# Signalwandler.net
KiCad netlist of a schematic drawn in EAGLE
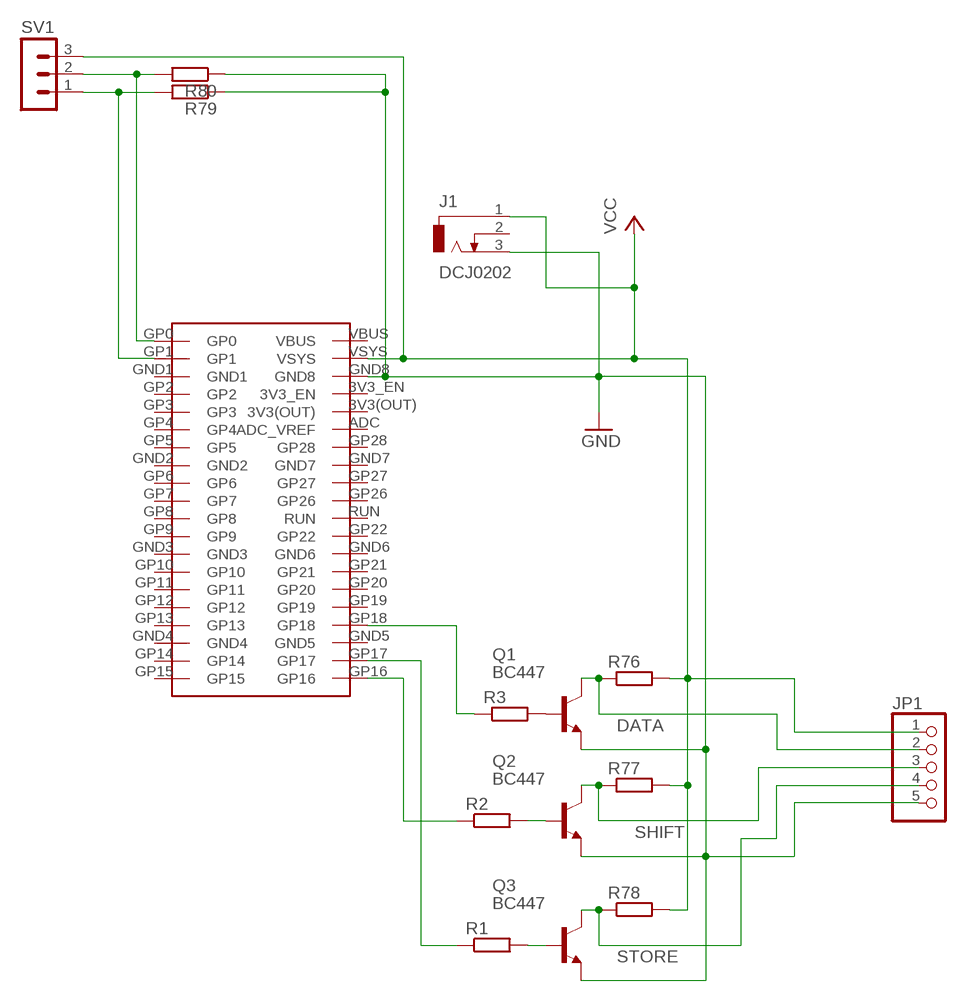
[diagram p0: schematic, sheet 1]

(export (version "E")
  (design (tool "Eeschema 10.0.6"))
  (components
    (comp (ref "J1")
      (value "DCJ0202")
      (footprint "eagle-import:DCJ0202")
      (libsource (lib "eagle-import") (part "DCJ0202"))
    )
    (comp (ref "JP1")
      (value "PINHD-1X5")
      (footprint "eagle-import:1X05")
      (libsource (lib "eagle-import") (part "PINHD-1X5"))
    )
    (comp (ref "Q1")
      (value "BC447")
      (footprint "eagle-import:TO92-EBC")
      (libsource (lib "eagle-import") (part "BC447"))
    )
    (comp (ref "Q2")
      (value "BC447")
      (footprint "eagle-import:TO92-EBC")
      (libsource (lib "eagle-import") (part "BC447"))
    )
    (comp (ref "Q3")
      (value "BC447")
      (footprint "eagle-import:TO92-EBC")
      (libsource (lib "eagle-import") (part "BC447"))
    )
    (comp (ref "R1")
      (value "R-EU_0207/10")
      (footprint "eagle-import:0207_10")
      (libsource (lib "eagle-import") (part "R-EU_0207/10"))
    )
    (comp (ref "R2")
      (value "R-EU_0207/10")
      (footprint "eagle-import:0207_10")
      (libsource (lib "eagle-import") (part "R-EU_0207/10"))
    )
    (comp (ref "R3")
      (value "R-EU_0207/10")
      (footprint "eagle-import:0207_10")
      (libsource (lib "eagle-import") (part "R-EU_0207/10"))
    )
    (comp (ref "R76")
      (value "R-EU_0207/10")
      (footprint "eagle-import:0207_10")
      (libsource (lib "eagle-import") (part "R-EU_0207/10"))
    )
    (comp (ref "R77")
      (value "R-EU_0207/10")
      (footprint "eagle-import:0207_10")
      (libsource (lib "eagle-import") (part "R-EU_0207/10"))
    )
    (comp (ref "R78")
      (value "R-EU_0207/10")
      (footprint "eagle-import:0207_10")
      (libsource (lib "eagle-import") (part "R-EU_0207/10"))
    )
    (comp (ref "R79")
      (value "R-EU_0207/10")
      (footprint "eagle-import:0207_10")
      (libsource (lib "eagle-import") (part "R-EU_0207/10"))
    )
    (comp (ref "R80")
      (value "R-EU_0207/10")
      (footprint "eagle-import:0207_10")
      (libsource (lib "eagle-import") (part "R-EU_0207/10"))
    )
    (comp (ref "SV1")
      (value "MA03-1")
      (footprint "eagle-import:MA03-1")
      (libsource (lib "eagle-import") (part "MA03-1"))
    )
    (comp (ref "U$2")
      (value "PI_PICO")
      (footprint "eagle-import:PI_PICO")
      (libsource (lib "eagle-import") (part "PI_PICO"))
    )
  )
  (nets
    (net (code "1") (name "/DATA") (class "Default")
      (node (ref "JP1") (pin "2") (pinfunction "2_2") (pintype "passive"))
      (node (ref "Q1") (pin "C") (pinfunction "C_C") (pintype "passive"))
      (node (ref "R76") (pin "1") (pinfunction "1_1") (pintype "passive"))
    )
    (net (code "2") (name "/SHIFT") (class "Default")
      (node (ref "JP1") (pin "3") (pinfunction "3_3") (pintype "passive"))
      (node (ref "Q2") (pin "C") (pinfunction "C_C") (pintype "passive"))
      (node (ref "R77") (pin "1") (pinfunction "1_1") (pintype "passive"))
    )
    (net (code "3") (name "/STORE") (class "Default")
      (node (ref "JP1") (pin "4") (pinfunction "4_4") (pintype "passive"))
      (node (ref "Q3") (pin "C") (pinfunction "C_C") (pintype "passive"))
      (node (ref "R78") (pin "1") (pinfunction "1_1") (pintype "passive"))
    )
    (net (code "4") (name "GND") (class "Default")
      (node (ref "J1") (pin "3") (pinfunction "3_3") (pintype "passive"))
      (node (ref "JP1") (pin "5") (pinfunction "5_5") (pintype "passive"))
      (node (ref "Q1") (pin "E") (pinfunction "E_E") (pintype "passive"))
      (node (ref "Q2") (pin "E") (pinfunction "E_E") (pintype "passive"))
      (node (ref "Q3") (pin "E") (pinfunction "E_E") (pintype "passive"))
      (node (ref "R79") (pin "1") (pinfunction "1_1") (pintype "passive"))
      (node (ref "R80") (pin "1") (pinfunction "1_1") (pintype "passive"))
      (node (ref "U$2") (pin "GND8") (pinfunction "GND8_GND8") (pintype "bidirectional"))
    )
    (net (code "5") (name "Net-(Q1-PadB)") (class "Default")
      (node (ref "Q1") (pin "B") (pinfunction "B_B") (pintype "passive"))
      (node (ref "R3") (pin "2") (pinfunction "2_2") (pintype "passive"))
    )
    (net (code "6") (name "Net-(Q2-PadB)") (class "Default")
      (node (ref "Q2") (pin "B") (pinfunction "B_B") (pintype "passive"))
      (node (ref "R2") (pin "2") (pinfunction "2_2") (pintype "passive"))
    )
    (net (code "7") (name "Net-(Q3-PadB)") (class "Default")
      (node (ref "Q3") (pin "B") (pinfunction "B_B") (pintype "passive"))
      (node (ref "R1") (pin "2") (pinfunction "2_2") (pintype "passive"))
    )
    (net (code "8") (name "Net-(R1-Pad1)") (class "Default")
      (node (ref "R1") (pin "1") (pinfunction "1_1") (pintype "passive"))
      (node (ref "U$2") (pin "GP17") (pinfunction "GP17_GP17") (pintype "bidirectional"))
    )
    (net (code "9") (name "Net-(R2-Pad1)") (class "Default")
      (node (ref "R2") (pin "1") (pinfunction "1_1") (pintype "passive"))
      (node (ref "U$2") (pin "GP16") (pinfunction "GP16_GP16") (pintype "bidirectional"))
    )
    (net (code "10") (name "Net-(R3-Pad1)") (class "Default")
      (node (ref "R3") (pin "1") (pinfunction "1_1") (pintype "passive"))
      (node (ref "U$2") (pin "GP18") (pinfunction "GP18_GP18") (pintype "bidirectional"))
    )
    (net (code "11") (name "Net-(R79-Pad2)") (class "Default")
      (node (ref "R79") (pin "2") (pinfunction "2_2") (pintype "passive"))
      (node (ref "SV1") (pin "1") (pinfunction "1_1") (pintype "passive"))
      (node (ref "U$2") (pin "GP1") (pinfunction "GP1_GP1") (pintype "bidirectional"))
    )
    (net (code "12") (name "Net-(R80-Pad2)") (class "Default")
      (node (ref "R80") (pin "2") (pinfunction "2_2") (pintype "passive"))
      (node (ref "SV1") (pin "2") (pinfunction "2_2") (pintype "passive"))
      (node (ref "U$2") (pin "GP0") (pinfunction "GP0_GP0") (pintype "bidirectional"))
    )
    (net (code "13") (name "VCC") (class "Default")
      (node (ref "J1") (pin "1") (pinfunction "1_1") (pintype "passive"))
      (node (ref "JP1") (pin "1") (pinfunction "1_1") (pintype "passive"))
      (node (ref "R76") (pin "2") (pinfunction "2_2") (pintype "passive"))
      (node (ref "R77") (pin "2") (pinfunction "2_2") (pintype "passive"))
      (node (ref "R78") (pin "2") (pinfunction "2_2") (pintype "passive"))
      (node (ref "SV1") (pin "3") (pinfunction "3_3") (pintype "passive"))
      (node (ref "U$2") (pin "VSYS") (pinfunction "VSYS_VSYS") (pintype "bidirectional"))
    )
    (net (code "14") (name "unconnected-(J1-Pad2)") (class "Default")
      (node (ref "J1") (pin "2") (pinfunction "2_2") (pintype "passive"))
    )
    (net (code "15") (name "unconnected-(U$2-ADC_VREF-PadADC)") (class "Default")
      (node (ref "U$2") (pin "ADC") (pinfunction "ADC_VREF_ADC") (pintype "bidirectional"))
    )
    (net (code "16") (name "unconnected-(U$2-Pad3V3(OUT))") (class "Default")
      (node (ref "U$2") (pin "3V3(OUT)") (pinfunction "3V3(OUT)_3V3(OUT)") (pintype "bidirectional"))
    )
    (net (code "17") (name "unconnected-(U$2-Pad3V3_EN)") (class "Default")
      (node (ref "U$2") (pin "3V3_EN") (pinfunction "3V3_EN_3V3_EN") (pintype "bidirectional"))
    )
    (net (code "18") (name "unconnected-(U$2-PadGND1)") (class "Default")
      (node (ref "U$2") (pin "GND1") (pinfunction "GND1_GND1") (pintype "bidirectional"))
    )
    (net (code "19") (name "unconnected-(U$2-PadGND2)") (class "Default")
      (node (ref "U$2") (pin "GND2") (pinfunction "GND2_GND2") (pintype "bidirectional"))
    )
    (net (code "20") (name "unconnected-(U$2-PadGND3)") (class "Default")
      (node (ref "U$2") (pin "GND3") (pinfunction "GND3_GND3") (pintype "bidirectional"))
    )
    (net (code "21") (name "unconnected-(U$2-PadGND4)") (class "Default")
      (node (ref "U$2") (pin "GND4") (pinfunction "GND4_GND4") (pintype "bidirectional"))
    )
    (net (code "22") (name "unconnected-(U$2-PadGND5)") (class "Default")
      (node (ref "U$2") (pin "GND5") (pinfunction "GND5_GND5") (pintype "bidirectional"))
    )
    (net (code "23") (name "unconnected-(U$2-PadGND6)") (class "Default")
      (node (ref "U$2") (pin "GND6") (pinfunction "GND6_GND6") (pintype "bidirectional"))
    )
    (net (code "24") (name "unconnected-(U$2-PadGND7)") (class "Default")
      (node (ref "U$2") (pin "GND7") (pinfunction "GND7_GND7") (pintype "bidirectional"))
    )
    (net (code "25") (name "unconnected-(U$2-PadGP2)") (class "Default")
      (node (ref "U$2") (pin "GP2") (pinfunction "GP2_GP2") (pintype "bidirectional"))
    )
    (net (code "26") (name "unconnected-(U$2-PadGP3)") (class "Default")
      (node (ref "U$2") (pin "GP3") (pinfunction "GP3_GP3") (pintype "bidirectional"))
    )
    (net (code "27") (name "unconnected-(U$2-PadGP4)") (class "Default")
      (node (ref "U$2") (pin "GP4") (pinfunction "GP4_GP4") (pintype "bidirectional"))
    )
    (net (code "28") (name "unconnected-(U$2-PadGP5)") (class "Default")
      (node (ref "U$2") (pin "GP5") (pinfunction "GP5_GP5") (pintype "bidirectional"))
    )
    (net (code "29") (name "unconnected-(U$2-PadGP6)") (class "Default")
      (node (ref "U$2") (pin "GP6") (pinfunction "GP6_GP6") (pintype "bidirectional"))
    )
    (net (code "30") (name "unconnected-(U$2-PadGP7)") (class "Default")
      (node (ref "U$2") (pin "GP7") (pinfunction "GP7_GP7") (pintype "bidirectional"))
    )
    (net (code "31") (name "unconnected-(U$2-PadGP8)") (class "Default")
      (node (ref "U$2") (pin "GP8") (pinfunction "GP8_GP8") (pintype "bidirectional"))
    )
    (net (code "32") (name "unconnected-(U$2-PadGP9)") (class "Default")
      (node (ref "U$2") (pin "GP9") (pinfunction "GP9_GP9") (pintype "bidirectional"))
    )
    (net (code "33") (name "unconnected-(U$2-PadGP10)") (class "Default")
      (node (ref "U$2") (pin "GP10") (pinfunction "GP10_GP10") (pintype "bidirectional"))
    )
    (net (code "34") (name "unconnected-(U$2-PadGP11)") (class "Default")
      (node (ref "U$2") (pin "GP11") (pinfunction "GP11_GP11") (pintype "bidirectional"))
    )
    (net (code "35") (name "unconnected-(U$2-PadGP12)") (class "Default")
      (node (ref "U$2") (pin "GP12") (pinfunction "GP12_GP12") (pintype "bidirectional"))
    )
    (net (code "36") (name "unconnected-(U$2-PadGP13)") (class "Default")
      (node (ref "U$2") (pin "GP13") (pinfunction "GP13_GP13") (pintype "bidirectional"))
    )
    (net (code "37") (name "unconnected-(U$2-PadGP14)") (class "Default")
      (node (ref "U$2") (pin "GP14") (pinfunction "GP14_GP14") (pintype "bidirectional"))
    )
    (net (code "38") (name "unconnected-(U$2-PadGP15)") (class "Default")
      (node (ref "U$2") (pin "GP15") (pinfunction "GP15_GP15") (pintype "bidirectional"))
    )
    (net (code "39") (name "unconnected-(U$2-PadGP19)") (class "Default")
      (node (ref "U$2") (pin "GP19") (pinfunction "GP19_GP19") (pintype "bidirectional"))
    )
    (net (code "40") (name "unconnected-(U$2-PadGP20)") (class "Default")
      (node (ref "U$2") (pin "GP20") (pinfunction "GP20_GP20") (pintype "bidirectional"))
    )
    (net (code "41") (name "unconnected-(U$2-PadGP21)") (class "Default")
      (node (ref "U$2") (pin "GP21") (pinfunction "GP21_GP21") (pintype "bidirectional"))
    )
    (net (code "42") (name "unconnected-(U$2-PadGP22)") (class "Default")
      (node (ref "U$2") (pin "GP22") (pinfunction "GP22_GP22") (pintype "bidirectional"))
    )
    (net (code "43") (name "unconnected-(U$2-PadGP26)") (class "Default")
      (node (ref "U$2") (pin "GP26") (pinfunction "GP26_GP26") (pintype "bidirectional"))
    )
    (net (code "44") (name "unconnected-(U$2-PadGP27)") (class "Default")
      (node (ref "U$2") (pin "GP27") (pinfunction "GP27_GP27") (pintype "bidirectional"))
    )
    (net (code "45") (name "unconnected-(U$2-PadGP28)") (class "Default")
      (node (ref "U$2") (pin "GP28") (pinfunction "GP28_GP28") (pintype "bidirectional"))
    )
    (net (code "46") (name "unconnected-(U$2-PadRUN)") (class "Default")
      (node (ref "U$2") (pin "RUN") (pinfunction "RUN_RUN") (pintype "bidirectional"))
    )
    (net (code "47") (name "unconnected-(U$2-PadVBUS)") (class "Default")
      (node (ref "U$2") (pin "VBUS") (pinfunction "VBUS_VBUS") (pintype "bidirectional"))
    )
  )
)
